# MECHANICAL.net
KiCad netlist of a schematic drawn in Altium Designer
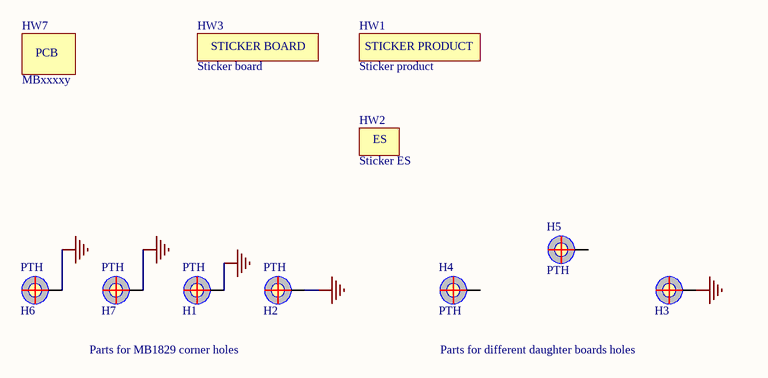
[diagram p0: MECHANICAL.SchDoc]

(export (version "E")
  (design (tool "Eeschema 10.0.6"))
  (components
    (comp (ref "H1")
      (value "PTH")
      (footprint "MCD_PARTS:PTH_350_700_H-12")
      (description "Position hole,  C7D3R5 with 12mm M3 pillar on bottom")
      (fields (field (name "INTERNAL_PART_NUMBER") "MCD-02916") (field (name "Comment") "POSITION HOLE"))
      (libsource (lib "MCD_PARTS_database") (part "POSITION HOLE"))
    )
    (comp (ref "H2")
      (value "PTH")
      (footprint "MCD_PARTS:PTH_350_700_H-12")
      (description "Position hole,  C7D3R5 with 12mm M3 pillar on bottom")
      (fields (field (name "INTERNAL_PART_NUMBER") "MCD-02916") (field (name "Comment") "POSITION HOLE"))
      (libsource (lib "MCD_PARTS_database") (part "POSITION HOLE"))
    )
    (comp (ref "H3")
      (value "POSITION HOLE")
      (footprint "MCD_PARTS:PTH_450_900")
      (description "POSITION HOLE C9D4R5")
      (fields (field (name "INTERNAL_PART_NUMBER") "MCD-01612"))
      (libsource (lib "MCD_PARTS_database") (part "POSITION HOLE"))
    )
    (comp (ref "H4")
      (value "PTH")
      (footprint "MCD_PARTS:PTH_350_500")
      (description "Position Hole C5D3R5: with no pillar in 3D, with pad design = c500h350m510.")
      (fields (field (name "INTERNAL_PART_NUMBER") "MCD-02915") (field (name "Comment") "POSITION HOLE"))
      (libsource (lib "MCD_PARTS_database") (part "POSITION HOLE"))
    )
    (comp (ref "H5")
      (value "PTH")
      (footprint "MCD_PARTS:PTH_350_500")
      (description "Position Hole C5D3R5: with no pillar in 3D, with pad design = c500h350m510.")
      (fields (field (name "INTERNAL_PART_NUMBER") "MCD-02915") (field (name "Comment") "POSITION HOLE"))
      (libsource (lib "MCD_PARTS_database") (part "POSITION HOLE"))
    )
    (comp (ref "H6")
      (value "PTH")
      (footprint "MCD_PARTS:PTH_350_700_H-12")
      (description "Position hole,  C7D3R5 with 12mm M3 pillar on bottom")
      (fields (field (name "INTERNAL_PART_NUMBER") "MCD-02916") (field (name "Comment") "POSITION HOLE"))
      (libsource (lib "MCD_PARTS_database") (part "POSITION HOLE"))
    )
    (comp (ref "H7")
      (value "PTH")
      (footprint "MCD_PARTS:PTH_350_700_H-12")
      (description "Position hole,  C7D3R5 with 12mm M3 pillar on bottom")
      (fields (field (name "INTERNAL_PART_NUMBER") "MCD-02916") (field (name "Comment") "POSITION HOLE"))
      (libsource (lib "MCD_PARTS_database") (part "POSITION HOLE"))
    )
    (comp (ref "HW1")
      (value "Sticker product")
      (footprint "MCD_PARTS:STICKER_PRODUCT_25X5")
      (description "Sticker product 25x5 mm")
      (fields (field (name "INTERNAL_PART_NUMBER") "MCD-02189") (field (name "Comment") "STICKER_PRODUCT"))
      (libsource (lib "MCD_PARTS_database") (part "STICKER_PRODUCT"))
    )
    (comp (ref "HW2")
      (value "Sticker ES")
      (footprint "MCD_PARTS:STICKER_ES_6X6")
      (description "Sticker ES 6x6 mm")
      (fields (field (name "INTERNAL_PART_NUMBER") "MCD-00234") (field (name "Comment") "STICKER_ES"))
      (libsource (lib "MCD_PARTS_database") (part "STICKER_ES"))
    )
    (comp (ref "HW3")
      (value "Sticker board")
      (footprint "MCD_PARTS:STICKER_BOARD_25X9")
      (description "Sticker Board 25x9 mm")
      (fields (field (name "INTERNAL_PART_NUMBER") "MCD-00235") (field (name "Comment") "STICKER_BOARD"))
      (libsource (lib "MCD_PARTS_database") (part "STICKER_BOARD"))
    )
    (comp (ref "HW7")
      (value "MBxxxxy")
      (description "PCB, xxxx for PCB number, Y for PCB revision")
      (fields
        (field (name "INTERNAL_PART_NUMBER") "MCD-00216")
        (field (name "MANUFACTURER_PART_NUMBER") "n/a")
      )
      (libsource (lib "MCD_PARTS_database") (part "PCB"))
    )
  )
  (nets
    (net (code "1") (name "GND") (class "Default")
      (node (ref "H1") (pin "1") (pinfunction "1_1") (pintype "passive"))
      (node (ref "H2") (pin "1") (pinfunction "1_1") (pintype "passive"))
      (node (ref "H3") (pin "1") (pinfunction "1_1") (pintype "passive"))
      (node (ref "H6") (pin "1") (pinfunction "1_1") (pintype "passive"))
      (node (ref "H7") (pin "1") (pinfunction "1_1") (pintype "passive"))
    )
    (net (code "2") (name "unconnected-(H4-Pad1)") (class "Default")
      (node (ref "H4") (pin "1") (pinfunction "1_1") (pintype "passive"))
    )
    (net (code "3") (name "unconnected-(H5-Pad1)") (class "Default")
      (node (ref "H5") (pin "1") (pinfunction "1_1") (pintype "passive"))
    )
  )
)
